# SmartScale.net
KiCad netlist of a schematic drawn in Altium Designer
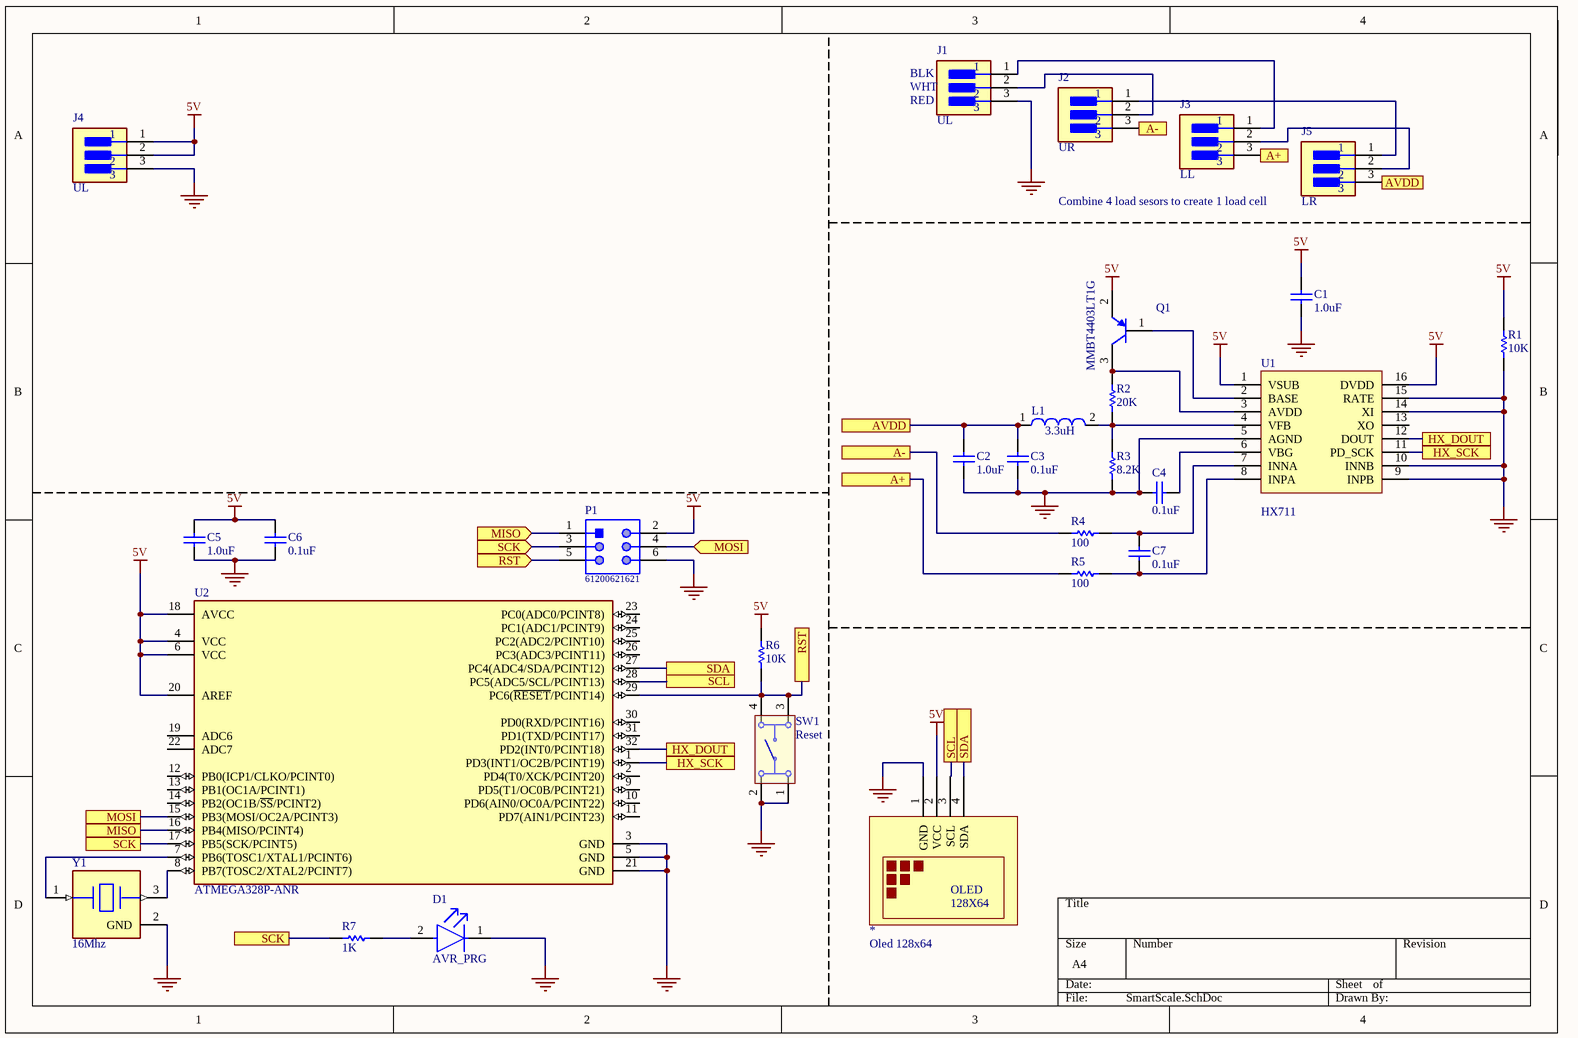
[diagram p0: SmartScale.SchDoc]

(export (version "E")
  (design (tool "Eeschema 10.0.6"))
  (components
    (comp (ref "*")
      (value "Oled 128x64")
      (footprint "OLED 128X64")
      (libsource (lib "SmartScale_Schlib1") (part "Oled 128x64"))
    )
    (comp (ref "C1")
      (value "1.0uF")
      (footprint "Cap_0805")
      (fields (field (name "MANUFACTURER") "Kemet") (field (name "PART NUMBER") "C0805C105K4PACTU"))
      (libsource (lib "SmartScale_Schlib1") (part "Cap_1.0uf"))
    )
    (comp (ref "C2")
      (value "1.0uF")
      (footprint "Cap_0805")
      (fields (field (name "MANUFACTURER") "Kemet") (field (name "PART NUMBER") "C0805C105K4PACTU"))
      (libsource (lib "SmartScale_Schlib1") (part "Cap_1.0uf"))
    )
    (comp (ref "C3")
      (value "0.1uF")
      (footprint "Cap_0805")
      (description "Cap Ceramic 100nF 100V X7R 10% Pad SMD 0805 +125°C Automotive T/R")
      (fields (field (name "TOLERANCE") "10%"))
      (libsource (lib "SmartScale_Schlib1") (part "Cap_0.1uf_0805"))
    )
    (comp (ref "C4")
      (value "0.1uF")
      (footprint "Cap_0805")
      (description "Cap Ceramic 100nF 100V X7R 10% Pad SMD 0805 +125°C Automotive T/R")
      (fields (field (name "TOLERANCE") "10%"))
      (libsource (lib "SmartScale_Schlib1") (part "Cap_0.1uf_0805"))
    )
    (comp (ref "C5")
      (value "1.0uF")
      (footprint "Cap_0805")
      (fields (field (name "MANUFACTURER") "Kemet") (field (name "PART NUMBER") "C0805C105K4PACTU"))
      (libsource (lib "SmartScale_Schlib1") (part "Cap_1.0uf"))
    )
    (comp (ref "C6")
      (value "0.1uF")
      (footprint "Cap_0805")
      (description "Cap Ceramic 100nF 100V X7R 10% Pad SMD 0805 +125°C Automotive T/R")
      (fields (field (name "TOLERANCE") "10%"))
      (libsource (lib "SmartScale_Schlib1") (part "Cap_0.1uf_0805"))
    )
    (comp (ref "C7")
      (value "0.1uF")
      (footprint "Cap_0805")
      (description "Cap Ceramic 100nF 100V X7R 10% Pad SMD 0805 +125°C Automotive T/R")
      (fields (field (name "TOLERANCE") "10%"))
      (libsource (lib "SmartScale_Schlib1") (part "Cap_0.1uf_0805"))
    )
    (comp (ref "D1")
      (value "AVR_PRG")
      (footprint "led_0805")
      (description "LED BLUE CLEAR CHIP SMD")
      (libsource (lib "SmartScale_Schlib1") (part "Led_0805"))
    )
    (comp (ref "J1")
      (value "UL")
      (footprint "CONN_1X3_SMD")
      (description "CONN HEADER SMD R/A 3POS 1.25MM")
      (fields
        (field (name "MANUFACTURER") "Molex")
        (field (name "OCTOPART") "https://octopart.com/53261-0371-molex-655314")
      )
      (libsource (lib "SmartScale_Schlib1") (part "CONN_1X3_SMD"))
    )
    (comp (ref "J2")
      (value "UR")
      (footprint "CONN_1X3_SMD")
      (description "CONN HEADER SMD R/A 3POS 1.25MM")
      (fields
        (field (name "MANUFACTURER") "Molex")
        (field (name "OCTOPART") "https://octopart.com/53261-0371-molex-655314")
      )
      (libsource (lib "SmartScale_Schlib1") (part "CONN_1X3_SMD"))
    )
    (comp (ref "J3")
      (value "LL")
      (footprint "CONN_1X3_SMD")
      (description "CONN HEADER SMD R/A 3POS 1.25MM")
      (fields
        (field (name "MANUFACTURER") "Molex")
        (field (name "OCTOPART") "https://octopart.com/53261-0371-molex-655314")
      )
      (libsource (lib "SmartScale_Schlib1") (part "CONN_1X3_SMD"))
    )
    (comp (ref "J4")
      (value "UL")
      (footprint "CONN_1X3_SMD")
      (description "CONN HEADER SMD R/A 3POS 1.25MM")
      (fields
        (field (name "MANUFACTURER") "Molex")
        (field (name "OCTOPART") "https://octopart.com/53261-0371-molex-655314")
      )
      (libsource (lib "SmartScale_Schlib1") (part "CONN_1X3_SMD"))
    )
    (comp (ref "J5")
      (value "LR")
      (footprint "CONN_1X3_SMD")
      (description "CONN HEADER SMD R/A 3POS 1.25MM")
      (fields
        (field (name "MANUFACTURER") "Molex")
        (field (name "OCTOPART") "https://octopart.com/53261-0371-molex-655314")
      )
      (libsource (lib "SmartScale_Schlib1") (part "CONN_1X3_SMD"))
    )
    (comp (ref "L1")
      (value "3.3uH")
      (footprint "SMD 0805_A")
      (description "Power Multilayer Inductor WE-PMI, L=3.30 µH")
      (fields (field (name "PARTNUMBER") "74479775233") (field (name "MANUFACTURER") "Wuerth Elektronik"))
      (libsource (lib "SmartScale_Schlib1") (part "COIL_3.3uH_0805"))
    )
    (comp (ref "P1")
      (value "61200621621")
      (footprint "BoxHeader_2*6")
      (description "Male Box Header WR-BHD, THT, Vertical, pitch 2.54 mm, 6 pins")
      (fields (field (name "MANUFACTURER") "Wurth Elektronik") (field (name "PUBLISHER") "WurthElektronik"))
      (libsource (lib "SmartScale_Schlib1") (part "BoxHeader_2*6"))
    )
    (comp (ref "Q1")
      (value "MMBT4403LT1G")
      (footprint "DIOD-SOT23-3_V")
      (description "Switching Transistor, PNP Silicon, 3-Pin SOT-23, Pb-Free, Tape and Reel")
      (fields (field (name "MANUFACTURER") "On Semiconductor"))
      (libsource (lib "SmartScale_Schlib1") (part "BJT"))
    )
    (comp (ref "R1")
      (value "10K")
      (footprint "Res_0805")
      (description "Chip Resistor, 10 KOhm, +/- 1%, 0.125 W, -55 to 155 degC, 0805 (2012 Metric), RoHS, Tape and Reel")
      (fields (field (name "MANUFACTURER") "Yageo"))
      (libsource (lib "SmartScale_Schlib1") (part "Res_10k_0805"))
    )
    (comp (ref "R2")
      (value "20K")
      (footprint "Res_0805")
      (fields (field (name "PART NUMBER") "CRCW080520K0JNEA") (field (name "MANUFACTURER") "Vishay Dale"))
      (libsource (lib "SmartScale_Schlib1") (part "RES_20K"))
    )
    (comp (ref "R3")
      (value "8.2K")
      (footprint "Res_0805")
      (fields (field (name "MANUFACTURER") "Panasonic") (field (name "PART NUMBER") "ERJ-6GEYJ822V"))
      (libsource (lib "SmartScale_Schlib1") (part "Res_8.2K"))
    )
    (comp (ref "R4")
      (value "100")
      (footprint "Res_0805")
      (fields (field (name "MANUFACTURER") "Vishay Dale") (field (name "PART NUMBER") "CRCW0805100RFKEA"))
      (libsource (lib "SmartScale_Schlib1") (part "Res_100"))
    )
    (comp (ref "R5")
      (value "100")
      (footprint "Res_0805")
      (fields (field (name "MANUFACTURER") "Vishay Dale") (field (name "PART NUMBER") "CRCW0805100RFKEA"))
      (libsource (lib "SmartScale_Schlib1") (part "Res_100"))
    )
    (comp (ref "R6")
      (value "10K")
      (footprint "Res_0805")
      (description "Chip Resistor, 10 KOhm, +/- 1%, 0.125 W, -55 to 155 degC, 0805 (2012 Metric), RoHS, Tape and Reel")
      (fields (field (name "MANUFACTURER") "Yageo"))
      (libsource (lib "SmartScale_Schlib1") (part "Res_10k_0805"))
    )
    (comp (ref "R7")
      (value "1K")
      (footprint "Res_0805")
      (description "Chip Resistor, 1 KOhm, +/- 1%, 125 mW, -55 to 155 degC, 0805 (2012 Metric), RoHS, Tape and Reel")
      (fields (field (name "TOLERANCE") "1%") (field (name "MANUFACTURER") "Yageo"))
      (libsource (lib "SmartScale_Schlib1") (part "res_1k_0805"))
    )
    (comp (ref "SW1")
      (value "Reset")
      (footprint "Button_smd")
      (description "WS-TASV SMD Tact Switch 6X6 mm")
      (fields (field (name "PARTNUMBER") "430451025836") (field (name "MANUFACTURER") "Wuerth Elektronik"))
      (libsource (lib "SmartScale_Schlib1") (part "Button_smd"))
    )
    (comp (ref "U1")
      (value "HX711")
      (footprint "TSOP16")
      (description "ADC for load cells")
      (libsource (lib "SmartScale_Schlib1") (part "HX711"))
    )
    (comp (ref "U2")
      (value "ATMEGA328P-ANR")
      (footprint "ATMEGA328P_TQFP")
      (description "IC MCU 8BIT 32KB FLASH 32TQFP")
      (libsource (lib "SmartScale_Schlib1") (part "ATMEGA328P_TQFP"))
    )
    (comp (ref "Y1")
      (value "16Mhz")
      (footprint "Resonator_16Mhz")
      (description "CERAMIC RES 16.0000MHZ 15PF SMD")
      (fields
        (field (name "TOLERANCE") "0.5%")
        (field (name "MANUFACTURER PART NUMBER") "CSTNE16M0V530000R0")
      )
      (libsource (lib "SmartScale_Schlib1") (part "Resonator_16Mhz"))
    )
  )
  (nets
    (net (code "1") (name "/A+") (class "Default")
      (node (ref "J3") (pin "3") (pinfunction "3_3") (pintype "passive"))
      (node (ref "R5") (pin "1") (pinfunction "1_1") (pintype "passive"))
    )
    (net (code "2") (name "/A-") (class "Default")
      (node (ref "J2") (pin "3") (pinfunction "3_3") (pintype "passive"))
      (node (ref "R4") (pin "1") (pinfunction "1_1") (pintype "passive"))
    )
    (net (code "3") (name "/AVDD") (class "Default")
      (node (ref "C2") (pin "2") (pinfunction "2_2") (pintype "passive"))
      (node (ref "C3") (pin "2") (pinfunction "2_2") (pintype "passive"))
      (node (ref "J5") (pin "3") (pinfunction "3_3") (pintype "passive"))
      (node (ref "L1") (pin "1") (pinfunction "1_1") (pintype "passive"))
    )
    (net (code "4") (name "/HX_DOUT") (class "Default")
      (node (ref "U1") (pin "12") (pinfunction "DOUT_12") (pintype "passive"))
      (node (ref "U2") (pin "32") (pinfunction "PD2(INT0/PCINT18)_32") (pintype "bidirectional"))
    )
    (net (code "5") (name "/HX_SCK") (class "Default")
      (node (ref "U1") (pin "11") (pinfunction "PD_SCK_11") (pintype "passive"))
      (node (ref "U2") (pin "1") (pinfunction "PD3(INT1/OC2B/PCINT19)_1") (pintype "bidirectional"))
    )
    (net (code "6") (name "/MISO") (class "Default")
      (node (ref "P1") (pin "1") (pinfunction "1_1") (pintype "passive"))
      (node (ref "U2") (pin "16") (pinfunction "PB4(MISO/PCINT4)_16") (pintype "bidirectional"))
    )
    (net (code "7") (name "/MOSI") (class "Default")
      (node (ref "P1") (pin "4") (pinfunction "4_4") (pintype "passive"))
      (node (ref "U2") (pin "15") (pinfunction "PB3(MOSI/OC2A/PCINT3)_15") (pintype "bidirectional"))
    )
    (net (code "8") (name "/RST") (class "Default")
      (node (ref "P1") (pin "5") (pinfunction "5_5") (pintype "passive"))
      (node (ref "R6") (pin "1") (pinfunction "1_1") (pintype "passive"))
      (node (ref "SW1") (pin "3") (pinfunction "3_3") (pintype "passive"))
      (node (ref "SW1") (pin "4") (pinfunction "4_4") (pintype "passive"))
      (node (ref "U2") (pin "29") (pinfunction "PC6(~{RESET}/PCINT14)_29") (pintype "bidirectional"))
    )
    (net (code "9") (name "/SCK") (class "Default")
      (node (ref "P1") (pin "3") (pinfunction "3_3") (pintype "passive"))
      (node (ref "R7") (pin "2") (pinfunction "2_2") (pintype "passive"))
      (node (ref "U2") (pin "17") (pinfunction "PB5(SCK/PCINT5)_17") (pintype "bidirectional"))
    )
    (net (code "10") (name "/SCL") (class "Default")
      (node (ref "*") (pin "3") (pinfunction "SCL_3") (pintype "passive"))
      (node (ref "U2") (pin "28") (pinfunction "PC5(ADC5/SCL/PCINT13)_28") (pintype "bidirectional"))
    )
    (net (code "11") (name "/SDA") (class "Default")
      (node (ref "*") (pin "4") (pinfunction "SDA_4") (pintype "passive"))
      (node (ref "U2") (pin "27") (pinfunction "PC4(ADC4/SDA/PCINT12)_27") (pintype "bidirectional"))
    )
    (net (code "12") (name "5V") (class "Default")
      (node (ref "*") (pin "2") (pinfunction "VCC_2") (pintype "passive"))
      (node (ref "C1") (pin "2") (pinfunction "2_2") (pintype "passive"))
      (node (ref "C5") (pin "2") (pinfunction "2_2") (pintype "passive"))
      (node (ref "C6") (pin "2") (pinfunction "2_2") (pintype "passive"))
      (node (ref "J4") (pin "1") (pinfunction "1_1") (pintype "passive"))
      (node (ref "J4") (pin "2") (pinfunction "2_2") (pintype "passive"))
      (node (ref "P1") (pin "2") (pinfunction "2_2") (pintype "passive"))
      (node (ref "Q1") (pin "2") (pinfunction "E_2") (pintype "passive"))
      (node (ref "R1") (pin "2") (pinfunction "2_2") (pintype "passive"))
      (node (ref "R6") (pin "2") (pinfunction "2_2") (pintype "passive"))
      (node (ref "U1") (pin "1") (pinfunction "VSUB_1") (pintype "passive"))
      (node (ref "U1") (pin "16") (pinfunction "DVDD_16") (pintype "passive"))
      (node (ref "U2") (pin "18") (pinfunction "AVCC_18") (pintype "power_in"))
      (node (ref "U2") (pin "20") (pinfunction "AREF_20") (pintype "passive"))
      (node (ref "U2") (pin "4") (pinfunction "VCC_4") (pintype "power_in"))
      (node (ref "U2") (pin "6") (pinfunction "VCC_6") (pintype "power_in"))
    )
    (net (code "13") (name "GND") (class "Default")
      (node (ref "*") (pin "1") (pinfunction "GND_1") (pintype "passive"))
      (node (ref "C1") (pin "1") (pinfunction "1_1") (pintype "passive"))
      (node (ref "C2") (pin "1") (pinfunction "1_1") (pintype "passive"))
      (node (ref "C3") (pin "1") (pinfunction "1_1") (pintype "passive"))
      (node (ref "C4") (pin "1") (pinfunction "1_1") (pintype "passive"))
      (node (ref "C5") (pin "1") (pinfunction "1_1") (pintype "passive"))
      (node (ref "C6") (pin "1") (pinfunction "1_1") (pintype "passive"))
      (node (ref "D1") (pin "1") (pinfunction "C_1") (pintype "passive"))
      (node (ref "J1") (pin "3") (pinfunction "3_3") (pintype "passive"))
      (node (ref "J4") (pin "3") (pinfunction "3_3") (pintype "passive"))
      (node (ref "P1") (pin "6") (pinfunction "6_6") (pintype "passive"))
      (node (ref "R1") (pin "1") (pinfunction "1_1") (pintype "passive"))
      (node (ref "R3") (pin "1") (pinfunction "1_1") (pintype "passive"))
      (node (ref "SW1") (pin "1") (pinfunction "1_1") (pintype "passive"))
      (node (ref "SW1") (pin "2") (pinfunction "2_2") (pintype "passive"))
      (node (ref "U1") (pin "10") (pinfunction "INNB_10") (pintype "passive"))
      (node (ref "U1") (pin "14") (pinfunction "XI_14") (pintype "passive"))
      (node (ref "U1") (pin "15") (pinfunction "RATE_15") (pintype "passive"))
      (node (ref "U1") (pin "5") (pinfunction "AGND_5") (pintype "passive"))
      (node (ref "U1") (pin "9") (pinfunction "INPB_9") (pintype "passive"))
      (node (ref "U2") (pin "21") (pinfunction "GND_21") (pintype "power_in"))
      (node (ref "U2") (pin "3") (pinfunction "GND_3") (pintype "power_in"))
      (node (ref "U2") (pin "5") (pinfunction "GND_5") (pintype "power_in"))
      (node (ref "Y1") (pin "2") (pinfunction "GND_2") (pintype "power_in"))
    )
    (net (code "14") (name "Net-(D1-A)") (class "Default")
      (node (ref "D1") (pin "2") (pinfunction "A_2") (pintype "passive"))
      (node (ref "R7") (pin "1") (pinfunction "1_1") (pintype "passive"))
    )
    (net (code "15") (name "Net-(J1-Pad1)") (class "Default")
      (node (ref "J1") (pin "1") (pinfunction "1_1") (pintype "passive"))
      (node (ref "J3") (pin "1") (pinfunction "1_1") (pintype "passive"))
    )
    (net (code "16") (name "Net-(J1-Pad2)") (class "Default")
      (node (ref "J1") (pin "2") (pinfunction "2_2") (pintype "passive"))
      (node (ref "J2") (pin "2") (pinfunction "2_2") (pintype "passive"))
    )
    (net (code "17") (name "Net-(J2-Pad1)") (class "Default")
      (node (ref "J2") (pin "1") (pinfunction "1_1") (pintype "passive"))
      (node (ref "J5") (pin "1") (pinfunction "1_1") (pintype "passive"))
    )
    (net (code "18") (name "Net-(J3-Pad2)") (class "Default")
      (node (ref "J3") (pin "2") (pinfunction "2_2") (pintype "passive"))
      (node (ref "J5") (pin "2") (pinfunction "2_2") (pintype "passive"))
    )
    (net (code "19") (name "Net-(Q1-B)") (class "Default")
      (node (ref "Q1") (pin "1") (pinfunction "B_1") (pintype "passive"))
      (node (ref "U1") (pin "2") (pinfunction "BASE_2") (pintype "passive"))
    )
    (net (code "20") (name "Net-(Q1-C)") (class "Default")
      (node (ref "Q1") (pin "3") (pinfunction "C_3") (pintype "passive"))
      (node (ref "R2") (pin "2") (pinfunction "2_2") (pintype "passive"))
      (node (ref "U1") (pin "3") (pinfunction "AVDD_3") (pintype "passive"))
    )
    (net (code "21") (name "Net-(U1-INNA)") (class "Default")
      (node (ref "C7") (pin "2") (pinfunction "2_2") (pintype "passive"))
      (node (ref "R4") (pin "2") (pinfunction "2_2") (pintype "passive"))
      (node (ref "U1") (pin "7") (pinfunction "INNA_7") (pintype "passive"))
    )
    (net (code "22") (name "Net-(U1-INPA)") (class "Default")
      (node (ref "C7") (pin "1") (pinfunction "1_1") (pintype "passive"))
      (node (ref "R5") (pin "2") (pinfunction "2_2") (pintype "passive"))
      (node (ref "U1") (pin "8") (pinfunction "INPA_8") (pintype "passive"))
    )
    (net (code "23") (name "Net-(U1-VBG)") (class "Default")
      (node (ref "C4") (pin "2") (pinfunction "2_2") (pintype "passive"))
      (node (ref "U1") (pin "6") (pinfunction "VBG_6") (pintype "passive"))
    )
    (net (code "24") (name "Net-(U1-VFB)") (class "Default")
      (node (ref "L1") (pin "2") (pinfunction "2_2") (pintype "passive"))
      (node (ref "R2") (pin "1") (pinfunction "1_1") (pintype "passive"))
      (node (ref "R3") (pin "2") (pinfunction "2_2") (pintype "passive"))
      (node (ref "U1") (pin "4") (pinfunction "VFB_4") (pintype "passive"))
    )
    (net (code "25") (name "Net-(U2-PB6(TOSC1{slash}XTAL1{slash}PCINT6))") (class "Default")
      (node (ref "U2") (pin "7") (pinfunction "PB6(TOSC1/XTAL1/PCINT6)_7") (pintype "bidirectional"))
      (node (ref "Y1") (pin "1") (pinfunction "Input_1") (pintype "input"))
    )
    (net (code "26") (name "Net-(U2-PB7(TOSC2{slash}XTAL2{slash}PCINT7))") (class "Default")
      (node (ref "U2") (pin "8") (pinfunction "PB7(TOSC2/XTAL2/PCINT7)_8") (pintype "bidirectional"))
      (node (ref "Y1") (pin "3") (pinfunction "Output_3") (pintype "output"))
    )
    (net (code "27") (name "unconnected-(U1-XO-Pad13)") (class "Default")
      (node (ref "U1") (pin "13") (pinfunction "XO_13") (pintype "passive"))
    )
    (net (code "28") (name "unconnected-(U2-ADC6-Pad19)") (class "Default")
      (node (ref "U2") (pin "19") (pinfunction "ADC6_19") (pintype "passive"))
    )
    (net (code "29") (name "unconnected-(U2-ADC7-Pad22)") (class "Default")
      (node (ref "U2") (pin "22") (pinfunction "ADC7_22") (pintype "passive"))
    )
    (net (code "30") (name "unconnected-(U2-PB0(ICP1{slash}CLKO{slash}PCINT0)-Pad12)") (class "Default")
      (node (ref "U2") (pin "12") (pinfunction "PB0(ICP1/CLKO/PCINT0)_12") (pintype "bidirectional"))
    )
    (net (code "31") (name "unconnected-(U2-PB1(OC1A{slash}PCINT1)-Pad13)") (class "Default")
      (node (ref "U2") (pin "13") (pinfunction "PB1(OC1A/PCINT1)_13") (pintype "bidirectional"))
    )
    (net (code "32") (name "unconnected-(U2-PB2(OC1B{slash}~{SS}{slash}PCINT2)-Pad14)") (class "Default")
      (node (ref "U2") (pin "14") (pinfunction "PB2(OC1B/~{SS}/PCINT2)_14") (pintype "bidirectional"))
    )
    (net (code "33") (name "unconnected-(U2-PC0(ADC0{slash}PCINT8)-Pad23)") (class "Default")
      (node (ref "U2") (pin "23") (pinfunction "PC0(ADC0/PCINT8)_23") (pintype "bidirectional"))
    )
    (net (code "34") (name "unconnected-(U2-PC1(ADC1{slash}PCINT9)-Pad24)") (class "Default")
      (node (ref "U2") (pin "24") (pinfunction "PC1(ADC1/PCINT9)_24") (pintype "bidirectional"))
    )
    (net (code "35") (name "unconnected-(U2-PC2(ADC2{slash}PCINT10)-Pad25)") (class "Default")
      (node (ref "U2") (pin "25") (pinfunction "PC2(ADC2/PCINT10)_25") (pintype "bidirectional"))
    )
    (net (code "36") (name "unconnected-(U2-PC3(ADC3{slash}PCINT11)-Pad26)") (class "Default")
      (node (ref "U2") (pin "26") (pinfunction "PC3(ADC3/PCINT11)_26") (pintype "bidirectional"))
    )
    (net (code "37") (name "unconnected-(U2-PD0(RXD{slash}PCINT16)-Pad30)") (class "Default")
      (node (ref "U2") (pin "30") (pinfunction "PD0(RXD/PCINT16)_30") (pintype "bidirectional"))
    )
    (net (code "38") (name "unconnected-(U2-PD1(TXD{slash}PCINT17)-Pad31)") (class "Default")
      (node (ref "U2") (pin "31") (pinfunction "PD1(TXD/PCINT17)_31") (pintype "bidirectional"))
    )
    (net (code "39") (name "unconnected-(U2-PD4(T0{slash}XCK{slash}PCINT20)-Pad2)") (class "Default")
      (node (ref "U2") (pin "2") (pinfunction "PD4(T0/XCK/PCINT20)_2") (pintype "bidirectional"))
    )
    (net (code "40") (name "unconnected-(U2-PD5(T1{slash}OC0B{slash}PCINT21)-Pad9)") (class "Default")
      (node (ref "U2") (pin "9") (pinfunction "PD5(T1/OC0B/PCINT21)_9") (pintype "bidirectional"))
    )
    (net (code "41") (name "unconnected-(U2-PD6(AIN0{slash}OC0A{slash}PCINT22)-Pad10)") (class "Default")
      (node (ref "U2") (pin "10") (pinfunction "PD6(AIN0/OC0A/PCINT22)_10") (pintype "bidirectional"))
    )
    (net (code "42") (name "unconnected-(U2-PD7(AIN1{slash}PCINT23)-Pad11)") (class "Default")
      (node (ref "U2") (pin "11") (pinfunction "PD7(AIN1/PCINT23)_11") (pintype "bidirectional"))
    )
  )
)
